# 4-Expand.net
KiCad netlist of a schematic drawn in Altium Designer
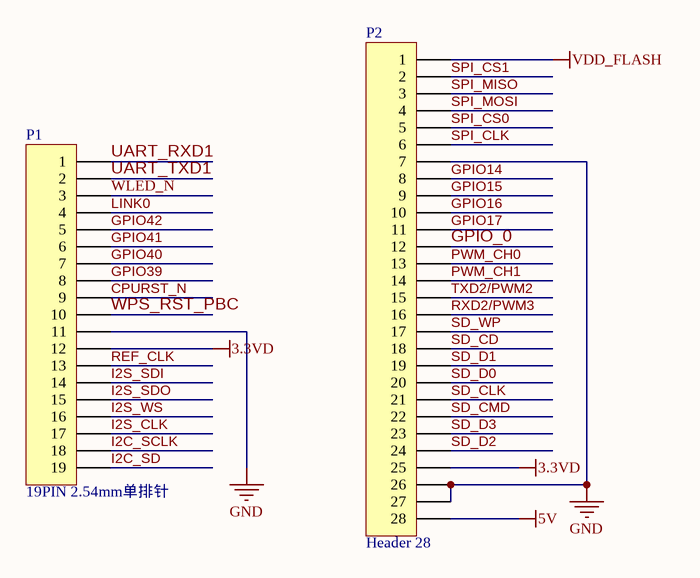
[diagram p0: 4-Expand.SchDoc]

(export (version "E")
  (design (tool "Eeschema 10.0.6"))
  (components
    (comp (ref "P1")
      (value "19PIN 2.54mm单排针")
      (footprint "HDR1X19")
      (description "Header, 19-Pin")
      (fields (field (name "PUBLISHER") "Altium Limited"))
      (libsource (lib "LIB_MANGO") (part "Header 19"))
    )
    (comp (ref "P2")
      (value "Header 28")
      (footprint "HDR1X28")
      (description "Header, 28-Pin")
      (fields (field (name "PUBLISHER") "Altium Limited"))
      (libsource (lib "LIB_MANGO") (part "Header 28"))
    )
  )
  (nets
    (net (code "1") (name "/CPURST_N") (class "Default")
      (node (ref "P1") (pin "9") (pinfunction "9_9") (pintype "passive"))
    )
    (net (code "2") (name "/GPIO14") (class "Default")
      (node (ref "P2") (pin "8") (pinfunction "8_8") (pintype "passive"))
    )
    (net (code "3") (name "/GPIO15") (class "Default")
      (node (ref "P2") (pin "9") (pinfunction "9_9") (pintype "passive"))
    )
    (net (code "4") (name "/GPIO16") (class "Default")
      (node (ref "P2") (pin "10") (pinfunction "10_10") (pintype "passive"))
    )
    (net (code "5") (name "/GPIO17") (class "Default")
      (node (ref "P2") (pin "11") (pinfunction "11_11") (pintype "passive"))
    )
    (net (code "6") (name "/GPIO39") (class "Default")
      (node (ref "P1") (pin "8") (pinfunction "8_8") (pintype "passive"))
    )
    (net (code "7") (name "/GPIO40") (class "Default")
      (node (ref "P1") (pin "7") (pinfunction "7_7") (pintype "passive"))
    )
    (net (code "8") (name "/GPIO41") (class "Default")
      (node (ref "P1") (pin "6") (pinfunction "6_6") (pintype "passive"))
    )
    (net (code "9") (name "/GPIO42") (class "Default")
      (node (ref "P1") (pin "5") (pinfunction "5_5") (pintype "passive"))
    )
    (net (code "10") (name "/GPIO_0") (class "Default")
      (node (ref "P2") (pin "12") (pinfunction "12_12") (pintype "passive"))
    )
    (net (code "11") (name "/I2C_SCLK") (class "Default")
      (node (ref "P1") (pin "18") (pinfunction "18_18") (pintype "passive"))
    )
    (net (code "12") (name "/I2C_SD") (class "Default")
      (node (ref "P1") (pin "19") (pinfunction "19_19") (pintype "passive"))
    )
    (net (code "13") (name "/I2S_CLK") (class "Default")
      (node (ref "P1") (pin "17") (pinfunction "17_17") (pintype "passive"))
    )
    (net (code "14") (name "/I2S_SDI") (class "Default")
      (node (ref "P1") (pin "14") (pinfunction "14_14") (pintype "passive"))
    )
    (net (code "15") (name "/I2S_SDO") (class "Default")
      (node (ref "P1") (pin "15") (pinfunction "15_15") (pintype "passive"))
    )
    (net (code "16") (name "/I2S_WS") (class "Default")
      (node (ref "P1") (pin "16") (pinfunction "16_16") (pintype "passive"))
    )
    (net (code "17") (name "/LINK0") (class "Default")
      (node (ref "P1") (pin "4") (pinfunction "4_4") (pintype "passive"))
    )
    (net (code "18") (name "/PWM_CH0") (class "Default")
      (node (ref "P2") (pin "13") (pinfunction "13_13") (pintype "passive"))
    )
    (net (code "19") (name "/PWM_CH1") (class "Default")
      (node (ref "P2") (pin "14") (pinfunction "14_14") (pintype "passive"))
    )
    (net (code "20") (name "/REF_CLK") (class "Default")
      (node (ref "P1") (pin "13") (pinfunction "13_13") (pintype "passive"))
    )
    (net (code "21") (name "/RXD2{slash}PWM3") (class "Default")
      (node (ref "P2") (pin "16") (pinfunction "16_16") (pintype "passive"))
    )
    (net (code "22") (name "/SD_CD") (class "Default")
      (node (ref "P2") (pin "18") (pinfunction "18_18") (pintype "passive"))
    )
    (net (code "23") (name "/SD_CLK") (class "Default")
      (node (ref "P2") (pin "21") (pinfunction "21_21") (pintype "passive"))
    )
    (net (code "24") (name "/SD_CMD") (class "Default")
      (node (ref "P2") (pin "22") (pinfunction "22_22") (pintype "passive"))
    )
    (net (code "25") (name "/SD_D0") (class "Default")
      (node (ref "P2") (pin "20") (pinfunction "20_20") (pintype "passive"))
    )
    (net (code "26") (name "/SD_D1") (class "Default")
      (node (ref "P2") (pin "19") (pinfunction "19_19") (pintype "passive"))
    )
    (net (code "27") (name "/SD_D2") (class "Default")
      (node (ref "P2") (pin "24") (pinfunction "24_24") (pintype "passive"))
    )
    (net (code "28") (name "/SD_D3") (class "Default")
      (node (ref "P2") (pin "23") (pinfunction "23_23") (pintype "passive"))
    )
    (net (code "29") (name "/SD_WP") (class "Default")
      (node (ref "P2") (pin "17") (pinfunction "17_17") (pintype "passive"))
    )
    (net (code "30") (name "/SPI_CLK") (class "Default")
      (node (ref "P2") (pin "6") (pinfunction "6_6") (pintype "passive"))
    )
    (net (code "31") (name "/SPI_CS0") (class "Default")
      (node (ref "P2") (pin "5") (pinfunction "5_5") (pintype "passive"))
    )
    (net (code "32") (name "/SPI_CS1") (class "Default")
      (node (ref "P2") (pin "2") (pinfunction "2_2") (pintype "passive"))
    )
    (net (code "33") (name "/SPI_MISO") (class "Default")
      (node (ref "P2") (pin "3") (pinfunction "3_3") (pintype "passive"))
    )
    (net (code "34") (name "/SPI_MOSI") (class "Default")
      (node (ref "P2") (pin "4") (pinfunction "4_4") (pintype "passive"))
    )
    (net (code "35") (name "/TXD2{slash}PWM2") (class "Default")
      (node (ref "P2") (pin "15") (pinfunction "15_15") (pintype "passive"))
    )
    (net (code "36") (name "/UART_RXD1") (class "Default")
      (node (ref "P1") (pin "1") (pinfunction "1_1") (pintype "passive"))
    )
    (net (code "37") (name "/UART_TXD1") (class "Default")
      (node (ref "P1") (pin "2") (pinfunction "2_2") (pintype "passive"))
    )
    (net (code "38") (name "/WLED_N") (class "Default")
      (node (ref "P1") (pin "3") (pinfunction "3_3") (pintype "passive"))
    )
    (net (code "39") (name "/WPS_RST_PBC") (class "Default")
      (node (ref "P1") (pin "10") (pinfunction "10_10") (pintype "passive"))
    )
    (net (code "40") (name "3.3VD") (class "Default")
      (node (ref "P1") (pin "12") (pinfunction "12_12") (pintype "passive"))
      (node (ref "P2") (pin "25") (pinfunction "25_25") (pintype "passive"))
    )
    (net (code "41") (name "5V") (class "Default")
      (node (ref "P2") (pin "28") (pinfunction "28_28") (pintype "passive"))
    )
    (net (code "42") (name "GND") (class "Default")
      (node (ref "P1") (pin "11") (pinfunction "11_11") (pintype "passive"))
      (node (ref "P2") (pin "26") (pinfunction "26_26") (pintype "passive"))
      (node (ref "P2") (pin "27") (pinfunction "27_27") (pintype "passive"))
      (node (ref "P2") (pin "7") (pinfunction "7_7") (pintype "passive"))
    )
    (net (code "43") (name "VDD_FLASH") (class "Default")
      (node (ref "P2") (pin "1") (pinfunction "1_1") (pintype "passive"))
    )
  )
)
